# clock_pulse_test.net
KiCad netlist of a schematic drawn in EAGLE
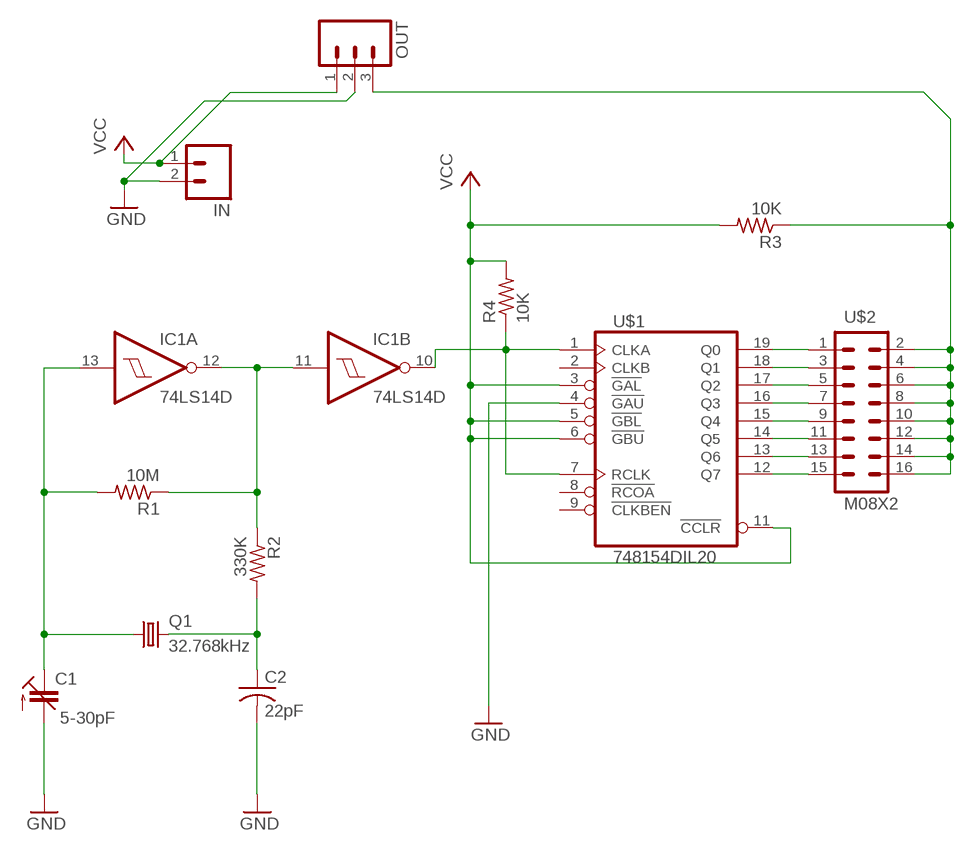
[diagram p0: schematic, sheet 1]

(export (version "E")
  (design (tool "Eeschema 10.0.6"))
  (components
    (comp (ref "C1")
      (value "5-30pF")
      (footprint "eagle-import:CTRIMTZ03")
      (libsource (lib "eagle-import") (part "C-TRIMMTZ03"))
    )
    (comp (ref "C2")
      (value "22pF")
      (footprint "eagle-import:C050-024X044")
      (libsource (lib "eagle-import") (part "CAPACITOR050-024X044"))
    )
    (comp (ref "IC1")
      (value "74LS14D")
      (footprint "eagle-import:SO14")
      (libsource (lib "eagle-import") (part "7414DLS"))
    )
    (comp (ref "IN")
      (value "M02PTH")
      (footprint "eagle-import:1X02")
      (libsource (lib "eagle-import") (part "M02PTH"))
    )
    (comp (ref "OUT")
      (value "M03PTH")
      (footprint "eagle-import:1X03")
      (libsource (lib "eagle-import") (part "M03PTH"))
    )
    (comp (ref "Q1")
      (value "32.768kHz")
      (footprint "eagle-import:TC26V")
      (libsource (lib "eagle-import") (part "CRYSTALTC26V"))
    )
    (comp (ref "R1")
      (value "10M")
      (footprint "eagle-import:0207_10")
      (libsource (lib "eagle-import") (part "RESISTOR0207/10"))
    )
    (comp (ref "R2")
      (value "330K")
      (footprint "eagle-import:0207_10")
      (libsource (lib "eagle-import") (part "RESISTOR0207/10"))
    )
    (comp (ref "R3")
      (value "10K")
      (footprint "eagle-import:0207_10")
      (libsource (lib "eagle-import") (part "RESISTOR0207/10"))
    )
    (comp (ref "R4")
      (value "10K")
      (footprint "eagle-import:0207_10")
      (libsource (lib "eagle-import") (part "RESISTOR0207/10"))
    )
    (comp (ref "U$1")
      (value "748154DIL20")
      (footprint "eagle-import:DIL20")
      (libsource (lib "eagle-import") (part "748154DIL20"))
    )
    (comp (ref "U$2")
      (value "M08X2")
      (footprint "eagle-import:2X8")
      (libsource (lib "eagle-import") (part "M08X2"))
    )
  )
  (nets
    (net (code "1") (name "GND") (class "Default")
      (node (ref "C1") (pin "2") (pinfunction "A_2") (pintype "passive"))
      (node (ref "C2") (pin "2") (pinfunction "2_2") (pintype "passive"))
      (node (ref "IN") (pin "2") (pinfunction "2_2") (pintype "passive"))
      (node (ref "OUT") (pin "2") (pinfunction "2_2") (pintype "passive"))
      (node (ref "U$1") (pin "4") (pinfunction "~{GAU}_4") (pintype "input"))
    )
    (net (code "2") (name "Net-(C1-E)") (class "Default")
      (node (ref "C1") (pin "1") (pinfunction "E_1") (pintype "passive"))
      (node (ref "IC1") (pin "13") (pinfunction "I_13") (pintype "input"))
      (node (ref "Q1") (pin "1") (pinfunction "1_1") (pintype "passive"))
      (node (ref "R1") (pin "2") (pinfunction "2_2") (pintype "passive"))
    )
    (net (code "3") (name "Net-(C2-Pad1)") (class "Default")
      (node (ref "C2") (pin "1") (pinfunction "1_1") (pintype "passive"))
      (node (ref "Q1") (pin "2") (pinfunction "2_2") (pintype "passive"))
      (node (ref "R2") (pin "2") (pinfunction "2_2") (pintype "passive"))
    )
    (net (code "4") (name "Net-(IC1A-O)") (class "Default")
      (node (ref "IC1") (pin "11") (pinfunction "I_11") (pintype "input"))
      (node (ref "IC1") (pin "12") (pinfunction "O_12") (pintype "output"))
      (node (ref "R1") (pin "1") (pinfunction "1_1") (pintype "passive"))
      (node (ref "R2") (pin "1") (pinfunction "1_1") (pintype "passive"))
    )
    (net (code "5") (name "Net-(IC1B-O)") (class "Default")
      (node (ref "IC1") (pin "10") (pinfunction "O_10") (pintype "output"))
      (node (ref "R4") (pin "1") (pinfunction "1_1") (pintype "passive"))
      (node (ref "U$1") (pin "1") (pinfunction "CLKA_1") (pintype "input"))
      (node (ref "U$1") (pin "7") (pinfunction "RCLK_7") (pintype "input"))
    )
    (net (code "6") (name "Net-(OUT-Pad3)") (class "Default")
      (node (ref "OUT") (pin "3") (pinfunction "3_3") (pintype "passive"))
      (node (ref "R3") (pin "1") (pinfunction "1_1") (pintype "passive"))
      (node (ref "U$2") (pin "10") (pinfunction "10_10") (pintype "passive"))
      (node (ref "U$2") (pin "12") (pinfunction "12_12") (pintype "passive"))
      (node (ref "U$2") (pin "14") (pinfunction "14_14") (pintype "passive"))
      (node (ref "U$2") (pin "16") (pinfunction "16_16") (pintype "passive"))
      (node (ref "U$2") (pin "2") (pinfunction "2_2") (pintype "passive"))
      (node (ref "U$2") (pin "4") (pinfunction "4_4") (pintype "passive"))
      (node (ref "U$2") (pin "6") (pinfunction "6_6") (pintype "passive"))
      (node (ref "U$2") (pin "8") (pinfunction "8_8") (pintype "passive"))
    )
    (net (code "7") (name "Net-(U$1A-Q0)") (class "Default")
      (node (ref "U$1") (pin "19") (pinfunction "Q0_19") (pintype "tri_state"))
      (node (ref "U$2") (pin "1") (pinfunction "1_1") (pintype "passive"))
    )
    (net (code "8") (name "Net-(U$1A-Q1)") (class "Default")
      (node (ref "U$1") (pin "18") (pinfunction "Q1_18") (pintype "tri_state"))
      (node (ref "U$2") (pin "3") (pinfunction "3_3") (pintype "passive"))
    )
    (net (code "9") (name "Net-(U$1A-Q2)") (class "Default")
      (node (ref "U$1") (pin "17") (pinfunction "Q2_17") (pintype "tri_state"))
      (node (ref "U$2") (pin "5") (pinfunction "5_5") (pintype "passive"))
    )
    (net (code "10") (name "Net-(U$1A-Q3)") (class "Default")
      (node (ref "U$1") (pin "16") (pinfunction "Q3_16") (pintype "tri_state"))
      (node (ref "U$2") (pin "7") (pinfunction "7_7") (pintype "passive"))
    )
    (net (code "11") (name "Net-(U$1A-Q4)") (class "Default")
      (node (ref "U$1") (pin "15") (pinfunction "Q4_15") (pintype "tri_state"))
      (node (ref "U$2") (pin "9") (pinfunction "9_9") (pintype "passive"))
    )
    (net (code "12") (name "Net-(U$1A-Q5)") (class "Default")
      (node (ref "U$1") (pin "14") (pinfunction "Q5_14") (pintype "tri_state"))
      (node (ref "U$2") (pin "11") (pinfunction "11_11") (pintype "passive"))
    )
    (net (code "13") (name "Net-(U$1A-Q6)") (class "Default")
      (node (ref "U$1") (pin "13") (pinfunction "Q6_13") (pintype "tri_state"))
      (node (ref "U$2") (pin "13") (pinfunction "13_13") (pintype "passive"))
    )
    (net (code "14") (name "Net-(U$1A-Q7)") (class "Default")
      (node (ref "U$1") (pin "12") (pinfunction "Q7_12") (pintype "tri_state"))
      (node (ref "U$2") (pin "15") (pinfunction "15_15") (pintype "passive"))
    )
    (net (code "15") (name "VCC") (class "Default")
      (node (ref "IN") (pin "1") (pinfunction "1_1") (pintype "passive"))
      (node (ref "OUT") (pin "1") (pinfunction "1_1") (pintype "passive"))
      (node (ref "R3") (pin "2") (pinfunction "2_2") (pintype "passive"))
      (node (ref "R4") (pin "2") (pinfunction "2_2") (pintype "passive"))
      (node (ref "U$1") (pin "11") (pinfunction "~{CCLR}_11") (pintype "output"))
      (node (ref "U$1") (pin "3") (pinfunction "~{GAL}_3") (pintype "input"))
      (node (ref "U$1") (pin "5") (pinfunction "~{GBL}_5") (pintype "input"))
      (node (ref "U$1") (pin "6") (pinfunction "~{GBU}_6") (pintype "input"))
    )
    (net (code "16") (name "unconnected-(U$1A-CLKB-Pad2)") (class "Default")
      (node (ref "U$1") (pin "2") (pinfunction "CLKB_2") (pintype "input"))
    )
    (net (code "17") (name "unconnected-(U$1A-~{CLKBEN}-Pad9)") (class "Default")
      (node (ref "U$1") (pin "9") (pinfunction "~{CLKBEN}_9") (pintype "input"))
    )
    (net (code "18") (name "unconnected-(U$1A-~{RCOA}-Pad8)") (class "Default")
      (node (ref "U$1") (pin "8") (pinfunction "~{RCOA}_8") (pintype "input"))
    )
  )
)
